# Face2.net
KiCad netlist of a schematic drawn in EAGLE
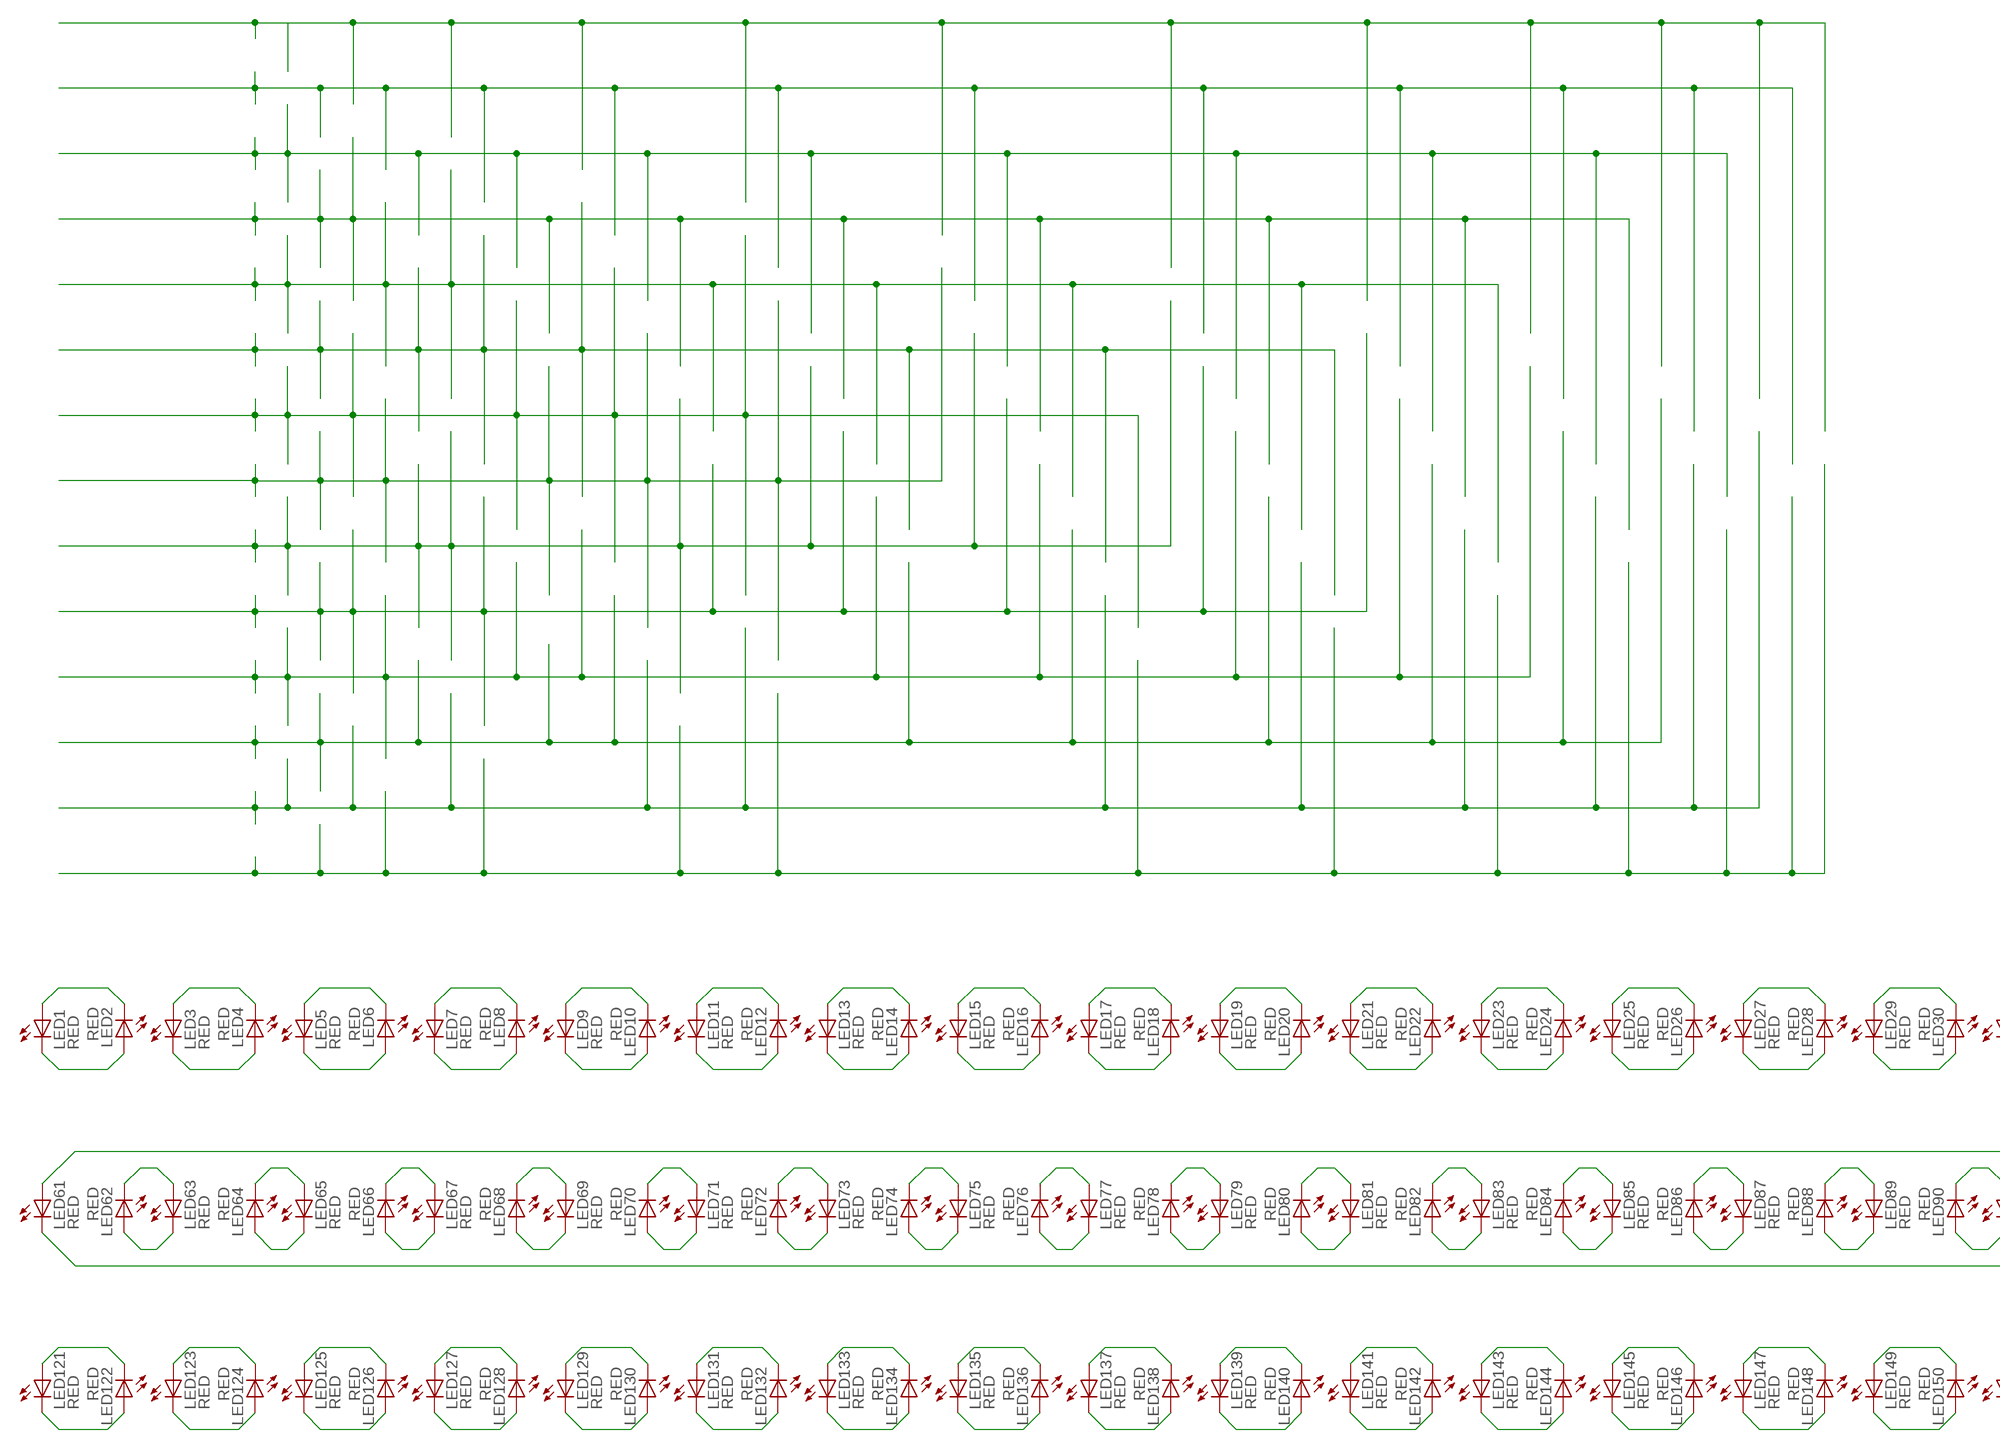
[diagram p0: schematic, sheet 1, part 1 of 2]
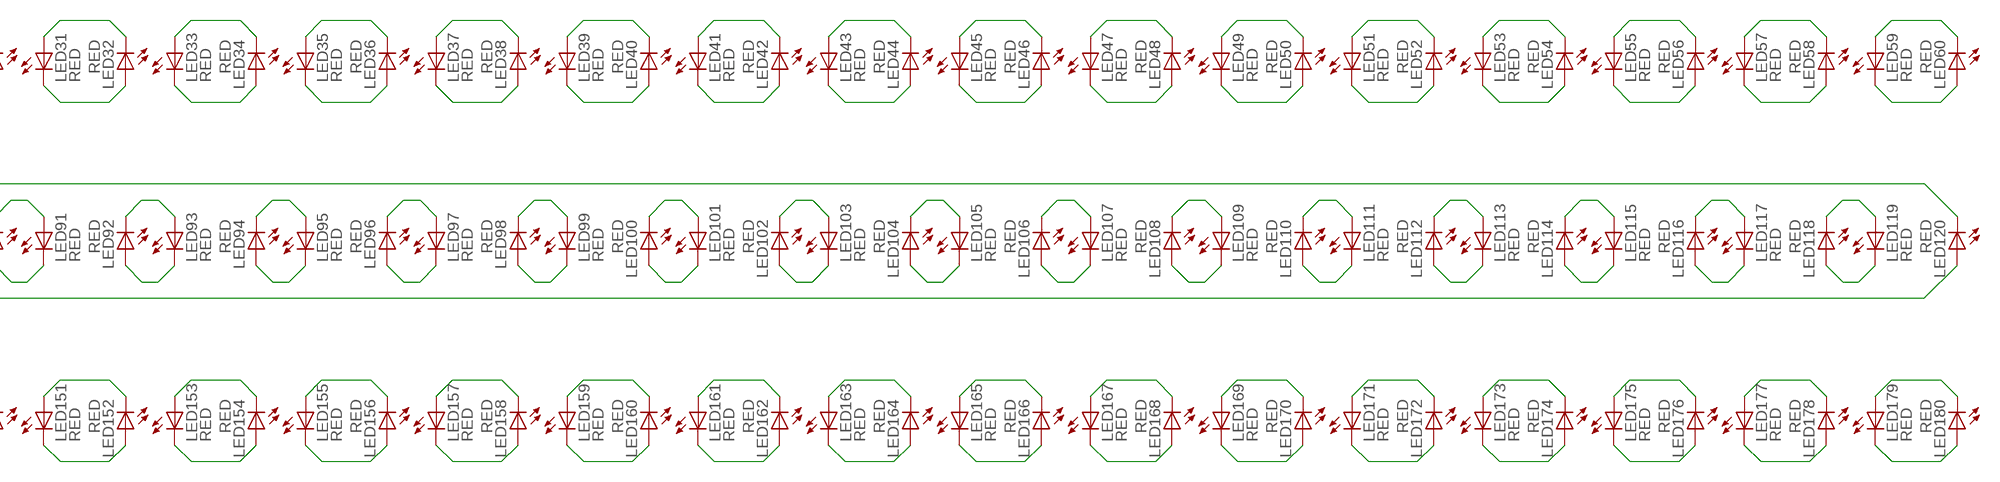
[diagram p1: schematic, sheet 1, part 2 of 2]

(export (version "E")
  (design (tool "Eeschema 10.0.6"))
  (components
    (comp (ref "LED1")
      (value "RED")
      (footprint "eagle-import:LED-0603")
      (libsource (lib "eagle-import") (part "LED0603"))
    )
    (comp (ref "LED2")
      (value "RED")
      (footprint "eagle-import:LED-0603")
      (libsource (lib "eagle-import") (part "LED0603"))
    )
    (comp (ref "LED3")
      (value "RED")
      (footprint "eagle-import:LED-0603")
      (libsource (lib "eagle-import") (part "LED0603"))
    )
    (comp (ref "LED4")
      (value "RED")
      (footprint "eagle-import:LED-0603")
      (libsource (lib "eagle-import") (part "LED0603"))
    )
    (comp (ref "LED5")
      (value "RED")
      (footprint "eagle-import:LED-0603")
      (libsource (lib "eagle-import") (part "LED0603"))
    )
    (comp (ref "LED6")
      (value "RED")
      (footprint "eagle-import:LED-0603")
      (libsource (lib "eagle-import") (part "LED0603"))
    )
    (comp (ref "LED7")
      (value "RED")
      (footprint "eagle-import:LED-0603")
      (libsource (lib "eagle-import") (part "LED0603"))
    )
    (comp (ref "LED8")
      (value "RED")
      (footprint "eagle-import:LED-0603")
      (libsource (lib "eagle-import") (part "LED0603"))
    )
    (comp (ref "LED9")
      (value "RED")
      (footprint "eagle-import:LED-0603")
      (libsource (lib "eagle-import") (part "LED0603"))
    )
    (comp (ref "LED10")
      (value "RED")
      (footprint "eagle-import:LED-0603")
      (libsource (lib "eagle-import") (part "LED0603"))
    )
    (comp (ref "LED11")
      (value "RED")
      (footprint "eagle-import:LED-0603")
      (libsource (lib "eagle-import") (part "LED0603"))
    )
    (comp (ref "LED12")
      (value "RED")
      (footprint "eagle-import:LED-0603")
      (libsource (lib "eagle-import") (part "LED0603"))
    )
    (comp (ref "LED13")
      (value "RED")
      (footprint "eagle-import:LED-0603")
      (libsource (lib "eagle-import") (part "LED0603"))
    )
    (comp (ref "LED14")
      (value "RED")
      (footprint "eagle-import:LED-0603")
      (libsource (lib "eagle-import") (part "LED0603"))
    )
    (comp (ref "LED15")
      (value "RED")
      (footprint "eagle-import:LED-0603")
      (libsource (lib "eagle-import") (part "LED0603"))
    )
    (comp (ref "LED16")
      (value "RED")
      (footprint "eagle-import:LED-0603")
      (libsource (lib "eagle-import") (part "LED0603"))
    )
    (comp (ref "LED17")
      (value "RED")
      (footprint "eagle-import:LED-0603")
      (libsource (lib "eagle-import") (part "LED0603"))
    )
    (comp (ref "LED18")
      (value "RED")
      (footprint "eagle-import:LED-0603")
      (libsource (lib "eagle-import") (part "LED0603"))
    )
    (comp (ref "LED19")
      (value "RED")
      (footprint "eagle-import:LED-0603")
      (libsource (lib "eagle-import") (part "LED0603"))
    )
    (comp (ref "LED20")
      (value "RED")
      (footprint "eagle-import:LED-0603")
      (libsource (lib "eagle-import") (part "LED0603"))
    )
    (comp (ref "LED21")
      (value "RED")
      (footprint "eagle-import:LED-0603")
      (libsource (lib "eagle-import") (part "LED0603"))
    )
    (comp (ref "LED22")
      (value "RED")
      (footprint "eagle-import:LED-0603")
      (libsource (lib "eagle-import") (part "LED0603"))
    )
    (comp (ref "LED23")
      (value "RED")
      (footprint "eagle-import:LED-0603")
      (libsource (lib "eagle-import") (part "LED0603"))
    )
    (comp (ref "LED24")
      (value "RED")
      (footprint "eagle-import:LED-0603")
      (libsource (lib "eagle-import") (part "LED0603"))
    )
    (comp (ref "LED25")
      (value "RED")
      (footprint "eagle-import:LED-0603")
      (libsource (lib "eagle-import") (part "LED0603"))
    )
    (comp (ref "LED26")
      (value "RED")
      (footprint "eagle-import:LED-0603")
      (libsource (lib "eagle-import") (part "LED0603"))
    )
    (comp (ref "LED27")
      (value "RED")
      (footprint "eagle-import:LED-0603")
      (libsource (lib "eagle-import") (part "LED0603"))
    )
    (comp (ref "LED28")
      (value "RED")
      (footprint "eagle-import:LED-0603")
      (libsource (lib "eagle-import") (part "LED0603"))
    )
    (comp (ref "LED29")
      (value "RED")
      (footprint "eagle-import:LED-0603")
      (libsource (lib "eagle-import") (part "LED0603"))
    )
    (comp (ref "LED30")
      (value "RED")
      (footprint "eagle-import:LED-0603")
      (libsource (lib "eagle-import") (part "LED0603"))
    )
    (comp (ref "LED31")
      (value "RED")
      (footprint "eagle-import:LED-0603")
      (libsource (lib "eagle-import") (part "LED0603"))
    )
    (comp (ref "LED32")
      (value "RED")
      (footprint "eagle-import:LED-0603")
      (libsource (lib "eagle-import") (part "LED0603"))
    )
    (comp (ref "LED33")
      (value "RED")
      (footprint "eagle-import:LED-0603")
      (libsource (lib "eagle-import") (part "LED0603"))
    )
    (comp (ref "LED34")
      (value "RED")
      (footprint "eagle-import:LED-0603")
      (libsource (lib "eagle-import") (part "LED0603"))
    )
    (comp (ref "LED35")
      (value "RED")
      (footprint "eagle-import:LED-0603")
      (libsource (lib "eagle-import") (part "LED0603"))
    )
    (comp (ref "LED36")
      (value "RED")
      (footprint "eagle-import:LED-0603")
      (libsource (lib "eagle-import") (part "LED0603"))
    )
    (comp (ref "LED37")
      (value "RED")
      (footprint "eagle-import:LED-0603")
      (libsource (lib "eagle-import") (part "LED0603"))
    )
    (comp (ref "LED38")
      (value "RED")
      (footprint "eagle-import:LED-0603")
      (libsource (lib "eagle-import") (part "LED0603"))
    )
    (comp (ref "LED39")
      (value "RED")
      (footprint "eagle-import:LED-0603")
      (libsource (lib "eagle-import") (part "LED0603"))
    )
    (comp (ref "LED40")
      (value "RED")
      (footprint "eagle-import:LED-0603")
      (libsource (lib "eagle-import") (part "LED0603"))
    )
    (comp (ref "LED41")
      (value "RED")
      (footprint "eagle-import:LED-0603")
      (libsource (lib "eagle-import") (part "LED0603"))
    )
    (comp (ref "LED42")
      (value "RED")
      (footprint "eagle-import:LED-0603")
      (libsource (lib "eagle-import") (part "LED0603"))
    )
    (comp (ref "LED43")
      (value "RED")
      (footprint "eagle-import:LED-0603")
      (libsource (lib "eagle-import") (part "LED0603"))
    )
    (comp (ref "LED44")
      (value "RED")
      (footprint "eagle-import:LED-0603")
      (libsource (lib "eagle-import") (part "LED0603"))
    )
    (comp (ref "LED45")
      (value "RED")
      (footprint "eagle-import:LED-0603")
      (libsource (lib "eagle-import") (part "LED0603"))
    )
    (comp (ref "LED46")
      (value "RED")
      (footprint "eagle-import:LED-0603")
      (libsource (lib "eagle-import") (part "LED0603"))
    )
    (comp (ref "LED47")
      (value "RED")
      (footprint "eagle-import:LED-0603")
      (libsource (lib "eagle-import") (part "LED0603"))
    )
    (comp (ref "LED48")
      (value "RED")
      (footprint "eagle-import:LED-0603")
      (libsource (lib "eagle-import") (part "LED0603"))
    )
    (comp (ref "LED49")
      (value "RED")
      (footprint "eagle-import:LED-0603")
      (libsource (lib "eagle-import") (part "LED0603"))
    )
    (comp (ref "LED50")
      (value "RED")
      (footprint "eagle-import:LED-0603")
      (libsource (lib "eagle-import") (part "LED0603"))
    )
    (comp (ref "LED51")
      (value "RED")
      (footprint "eagle-import:LED-0603")
      (libsource (lib "eagle-import") (part "LED0603"))
    )
    (comp (ref "LED52")
      (value "RED")
      (footprint "eagle-import:LED-0603")
      (libsource (lib "eagle-import") (part "LED0603"))
    )
    (comp (ref "LED53")
      (value "RED")
      (footprint "eagle-import:LED-0603")
      (libsource (lib "eagle-import") (part "LED0603"))
    )
    (comp (ref "LED54")
      (value "RED")
      (footprint "eagle-import:LED-0603")
      (libsource (lib "eagle-import") (part "LED0603"))
    )
    (comp (ref "LED55")
      (value "RED")
      (footprint "eagle-import:LED-0603")
      (libsource (lib "eagle-import") (part "LED0603"))
    )
    (comp (ref "LED56")
      (value "RED")
      (footprint "eagle-import:LED-0603")
      (libsource (lib "eagle-import") (part "LED0603"))
    )
    (comp (ref "LED57")
      (value "RED")
      (footprint "eagle-import:LED-0603")
      (libsource (lib "eagle-import") (part "LED0603"))
    )
    (comp (ref "LED58")
      (value "RED")
      (footprint "eagle-import:LED-0603")
      (libsource (lib "eagle-import") (part "LED0603"))
    )
    (comp (ref "LED59")
      (value "RED")
      (footprint "eagle-import:LED-0603")
      (libsource (lib "eagle-import") (part "LED0603"))
    )
    (comp (ref "LED60")
      (value "RED")
      (footprint "eagle-import:LED-0603")
      (libsource (lib "eagle-import") (part "LED0603"))
    )
    (comp (ref "LED61")
      (value "RED")
      (footprint "eagle-import:LED-0603")
      (libsource (lib "eagle-import") (part "LED0603"))
    )
    (comp (ref "LED62")
      (value "RED")
      (footprint "eagle-import:LED-0603")
      (libsource (lib "eagle-import") (part "LED0603"))
    )
    (comp (ref "LED63")
      (value "RED")
      (footprint "eagle-import:LED-0603")
      (libsource (lib "eagle-import") (part "LED0603"))
    )
    (comp (ref "LED64")
      (value "RED")
      (footprint "eagle-import:LED-0603")
      (libsource (lib "eagle-import") (part "LED0603"))
    )
    (comp (ref "LED65")
      (value "RED")
      (footprint "eagle-import:LED-0603")
      (libsource (lib "eagle-import") (part "LED0603"))
    )
    (comp (ref "LED66")
      (value "RED")
      (footprint "eagle-import:LED-0603")
      (libsource (lib "eagle-import") (part "LED0603"))
    )
    (comp (ref "LED67")
      (value "RED")
      (footprint "eagle-import:LED-0603")
      (libsource (lib "eagle-import") (part "LED0603"))
    )
    (comp (ref "LED68")
      (value "RED")
      (footprint "eagle-import:LED-0603")
      (libsource (lib "eagle-import") (part "LED0603"))
    )
    (comp (ref "LED69")
      (value "RED")
      (footprint "eagle-import:LED-0603")
      (libsource (lib "eagle-import") (part "LED0603"))
    )
    (comp (ref "LED70")
      (value "RED")
      (footprint "eagle-import:LED-0603")
      (libsource (lib "eagle-import") (part "LED0603"))
    )
    (comp (ref "LED71")
      (value "RED")
      (footprint "eagle-import:LED-0603")
      (libsource (lib "eagle-import") (part "LED0603"))
    )
    (comp (ref "LED72")
      (value "RED")
      (footprint "eagle-import:LED-0603")
      (libsource (lib "eagle-import") (part "LED0603"))
    )
    (comp (ref "LED73")
      (value "RED")
      (footprint "eagle-import:LED-0603")
      (libsource (lib "eagle-import") (part "LED0603"))
    )
    (comp (ref "LED74")
      (value "RED")
      (footprint "eagle-import:LED-0603")
      (libsource (lib "eagle-import") (part "LED0603"))
    )
    (comp (ref "LED75")
      (value "RED")
      (footprint "eagle-import:LED-0603")
      (libsource (lib "eagle-import") (part "LED0603"))
    )
    (comp (ref "LED76")
      (value "RED")
      (footprint "eagle-import:LED-0603")
      (libsource (lib "eagle-import") (part "LED0603"))
    )
    (comp (ref "LED77")
      (value "RED")
      (footprint "eagle-import:LED-0603")
      (libsource (lib "eagle-import") (part "LED0603"))
    )
    (comp (ref "LED78")
      (value "RED")
      (footprint "eagle-import:LED-0603")
      (libsource (lib "eagle-import") (part "LED0603"))
    )
    (comp (ref "LED79")
      (value "RED")
      (footprint "eagle-import:LED-0603")
      (libsource (lib "eagle-import") (part "LED0603"))
    )
    (comp (ref "LED80")
      (value "RED")
      (footprint "eagle-import:LED-0603")
      (libsource (lib "eagle-import") (part "LED0603"))
    )
    (comp (ref "LED81")
      (value "RED")
      (footprint "eagle-import:LED-0603")
      (libsource (lib "eagle-import") (part "LED0603"))
    )
    (comp (ref "LED82")
      (value "RED")
      (footprint "eagle-import:LED-0603")
      (libsource (lib "eagle-import") (part "LED0603"))
    )
    (comp (ref "LED83")
      (value "RED")
      (footprint "eagle-import:LED-0603")
      (libsource (lib "eagle-import") (part "LED0603"))
    )
    (comp (ref "LED84")
      (value "RED")
      (footprint "eagle-import:LED-0603")
      (libsource (lib "eagle-import") (part "LED0603"))
    )
    (comp (ref "LED85")
      (value "RED")
      (footprint "eagle-import:LED-0603")
      (libsource (lib "eagle-import") (part "LED0603"))
    )
    (comp (ref "LED86")
      (value "RED")
      (footprint "eagle-import:LED-0603")
      (libsource (lib "eagle-import") (part "LED0603"))
    )
    (comp (ref "LED87")
      (value "RED")
      (footprint "eagle-import:LED-0603")
      (libsource (lib "eagle-import") (part "LED0603"))
    )
    (comp (ref "LED88")
      (value "RED")
      (footprint "eagle-import:LED-0603")
      (libsource (lib "eagle-import") (part "LED0603"))
    )
    (comp (ref "LED89")
      (value "RED")
      (footprint "eagle-import:LED-0603")
      (libsource (lib "eagle-import") (part "LED0603"))
    )
    (comp (ref "LED90")
      (value "RED")
      (footprint "eagle-import:LED-0603")
      (libsource (lib "eagle-import") (part "LED0603"))
    )
    (comp (ref "LED91")
      (value "RED")
      (footprint "eagle-import:LED-0603")
      (libsource (lib "eagle-import") (part "LED0603"))
    )
    (comp (ref "LED92")
      (value "RED")
      (footprint "eagle-import:LED-0603")
      (libsource (lib "eagle-import") (part "LED0603"))
    )
    (comp (ref "LED93")
      (value "RED")
      (footprint "eagle-import:LED-0603")
      (libsource (lib "eagle-import") (part "LED0603"))
    )
    (comp (ref "LED94")
      (value "RED")
      (footprint "eagle-import:LED-0603")
      (libsource (lib "eagle-import") (part "LED0603"))
    )
    (comp (ref "LED95")
      (value "RED")
      (footprint "eagle-import:LED-0603")
      (libsource (lib "eagle-import") (part "LED0603"))
    )
    (comp (ref "LED96")
      (value "RED")
      (footprint "eagle-import:LED-0603")
      (libsource (lib "eagle-import") (part "LED0603"))
    )
    (comp (ref "LED97")
      (value "RED")
      (footprint "eagle-import:LED-0603")
      (libsource (lib "eagle-import") (part "LED0603"))
    )
    (comp (ref "LED98")
      (value "RED")
      (footprint "eagle-import:LED-0603")
      (libsource (lib "eagle-import") (part "LED0603"))
    )
    (comp (ref "LED99")
      (value "RED")
      (footprint "eagle-import:LED-0603")
      (libsource (lib "eagle-import") (part "LED0603"))
    )
    (comp (ref "LED100")
      (value "RED")
      (footprint "eagle-import:LED-0603")
      (libsource (lib "eagle-import") (part "LED0603"))
    )
    (comp (ref "LED101")
      (value "RED")
      (footprint "eagle-import:LED-0603")
      (libsource (lib "eagle-import") (part "LED0603"))
    )
    (comp (ref "LED102")
      (value "RED")
      (footprint "eagle-import:LED-0603")
      (libsource (lib "eagle-import") (part "LED0603"))
    )
    (comp (ref "LED103")
      (value "RED")
      (footprint "eagle-import:LED-0603")
      (libsource (lib "eagle-import") (part "LED0603"))
    )
    (comp (ref "LED104")
      (value "RED")
      (footprint "eagle-import:LED-0603")
      (libsource (lib "eagle-import") (part "LED0603"))
    )
    (comp (ref "LED105")
      (value "RED")
      (footprint "eagle-import:LED-0603")
      (libsource (lib "eagle-import") (part "LED0603"))
    )
    (comp (ref "LED106")
      (value "RED")
      (footprint "eagle-import:LED-0603")
      (libsource (lib "eagle-import") (part "LED0603"))
    )
    (comp (ref "LED107")
      (value "RED")
      (footprint "eagle-import:LED-0603")
      (libsource (lib "eagle-import") (part "LED0603"))
    )
    (comp (ref "LED108")
      (value "RED")
      (footprint "eagle-import:LED-0603")
      (libsource (lib "eagle-import") (part "LED0603"))
    )
    (comp (ref "LED109")
      (value "RED")
      (footprint "eagle-import:LED-0603")
      (libsource (lib "eagle-import") (part "LED0603"))
    )
    (comp (ref "LED110")
      (value "RED")
      (footprint "eagle-import:LED-0603")
      (libsource (lib "eagle-import") (part "LED0603"))
    )
    (comp (ref "LED111")
      (value "RED")
      (footprint "eagle-import:LED-0603")
      (libsource (lib "eagle-import") (part "LED0603"))
    )
    (comp (ref "LED112")
      (value "RED")
      (footprint "eagle-import:LED-0603")
      (libsource (lib "eagle-import") (part "LED0603"))
    )
    (comp (ref "LED113")
      (value "RED")
      (footprint "eagle-import:LED-0603")
      (libsource (lib "eagle-import") (part "LED0603"))
    )
    (comp (ref "LED114")
      (value "RED")
      (footprint "eagle-import:LED-0603")
      (libsource (lib "eagle-import") (part "LED0603"))
    )
    (comp (ref "LED115")
      (value "RED")
      (footprint "eagle-import:LED-0603")
      (libsource (lib "eagle-import") (part "LED0603"))
    )
    (comp (ref "LED116")
      (value "RED")
      (footprint "eagle-import:LED-0603")
      (libsource (lib "eagle-import") (part "LED0603"))
    )
    (comp (ref "LED117")
      (value "RED")
      (footprint "eagle-import:LED-0603")
      (libsource (lib "eagle-import") (part "LED0603"))
    )
    (comp (ref "LED118")
      (value "RED")
      (footprint "eagle-import:LED-0603")
      (libsource (lib "eagle-import") (part "LED0603"))
    )
    (comp (ref "LED119")
      (value "RED")
      (footprint "eagle-import:LED-0603")
      (libsource (lib "eagle-import") (part "LED0603"))
    )
    (comp (ref "LED120")
      (value "RED")
      (footprint "eagle-import:LED-0603")
      (libsource (lib "eagle-import") (part "LED0603"))
    )
    (comp (ref "LED121")
      (value "RED")
      (footprint "eagle-import:LED-0603")
      (libsource (lib "eagle-import") (part "LED0603"))
    )
    (comp (ref "LED122")
      (value "RED")
      (footprint "eagle-import:LED-0603")
      (libsource (lib "eagle-import") (part "LED0603"))
    )
    (comp (ref "LED123")
      (value "RED")
      (footprint "eagle-import:LED-0603")
      (libsource (lib "eagle-import") (part "LED0603"))
    )
    (comp (ref "LED124")
      (value "RED")
      (footprint "eagle-import:LED-0603")
      (libsource (lib "eagle-import") (part "LED0603"))
    )
    (comp (ref "LED125")
      (value "RED")
      (footprint "eagle-import:LED-0603")
      (libsource (lib "eagle-import") (part "LED0603"))
    )
    (comp (ref "LED126")
      (value "RED")
      (footprint "eagle-import:LED-0603")
      (libsource (lib "eagle-import") (part "LED0603"))
    )
    (comp (ref "LED127")
      (value "RED")
      (footprint "eagle-import:LED-0603")
      (libsource (lib "eagle-import") (part "LED0603"))
    )
    (comp (ref "LED128")
      (value "RED")
      (footprint "eagle-import:LED-0603")
      (libsource (lib "eagle-import") (part "LED0603"))
    )
    (comp (ref "LED129")
      (value "RED")
      (footprint "eagle-import:LED-0603")
      (libsource (lib "eagle-import") (part "LED0603"))
    )
    (comp (ref "LED130")
      (value "RED")
      (footprint "eagle-import:LED-0603")
      (libsource (lib "eagle-import") (part "LED0603"))
    )
    (comp (ref "LED131")
      (value "RED")
      (footprint "eagle-import:LED-0603")
      (libsource (lib "eagle-import") (part "LED0603"))
    )
    (comp (ref "LED132")
      (value "RED")
      (footprint "eagle-import:LED-0603")
      (libsource (lib "eagle-import") (part "LED0603"))
    )
    (comp (ref "LED133")
      (value "RED")
      (footprint "eagle-import:LED-0603")
      (libsource (lib "eagle-import") (part "LED0603"))
    )
    (comp (ref "LED134")
      (value "RED")
      (footprint "eagle-import:LED-0603")
      (libsource (lib "eagle-import") (part "LED0603"))
    )
    (comp (ref "LED135")
      (value "RED")
      (footprint "eagle-import:LED-0603")
      (libsource (lib "eagle-import") (part "LED0603"))
    )
    (comp (ref "LED136")
      (value "RED")
      (footprint "eagle-import:LED-0603")
      (libsource (lib "eagle-import") (part "LED0603"))
    )
    (comp (ref "LED137")
      (value "RED")
      (footprint "eagle-import:LED-0603")
      (libsource (lib "eagle-import") (part "LED0603"))
    )
    (comp (ref "LED138")
      (value "RED")
      (footprint "eagle-import:LED-0603")
      (libsource (lib "eagle-import") (part "LED0603"))
    )
    (comp (ref "LED139")
      (value "RED")
      (footprint "eagle-import:LED-0603")
      (libsource (lib "eagle-import") (part "LED0603"))
    )
    (comp (ref "LED140")
      (value "RED")
      (footprint "eagle-import:LED-0603")
      (libsource (lib "eagle-import") (part "LED0603"))
    )
    (comp (ref "LED141")
      (value "RED")
      (footprint "eagle-import:LED-0603")
      (libsource (lib "eagle-import") (part "LED0603"))
    )
    (comp (ref "LED142")
      (value "RED")
      (footprint "eagle-import:LED-0603")
      (libsource (lib "eagle-import") (part "LED0603"))
    )
    (comp (ref "LED143")
      (value "RED")
      (footprint "eagle-import:LED-0603")
      (libsource (lib "eagle-import") (part "LED0603"))
    )
    (comp (ref "LED144")
      (value "RED")
      (footprint "eagle-import:LED-0603")
      (libsource (lib "eagle-import") (part "LED0603"))
    )
    (comp (ref "LED145")
      (value "RED")
      (footprint "eagle-import:LED-0603")
      (libsource (lib "eagle-import") (part "LED0603"))
    )
    (comp (ref "LED146")
      (value "RED")
      (footprint "eagle-import:LED-0603")
      (libsource (lib "eagle-import") (part "LED0603"))
    )
    (comp (ref "LED147")
      (value "RED")
      (footprint "eagle-import:LED-0603")
      (libsource (lib "eagle-import") (part "LED0603"))
    )
    (comp (ref "LED148")
      (value "RED")
      (footprint "eagle-import:LED-0603")
      (libsource (lib "eagle-import") (part "LED0603"))
    )
    (comp (ref "LED149")
      (value "RED")
      (footprint "eagle-import:LED-0603")
      (libsource (lib "eagle-import") (part "LED0603"))
    )
    (comp (ref "LED150")
      (value "RED")
      (footprint "eagle-import:LED-0603")
      (libsource (lib "eagle-import") (part "LED0603"))
    )
    (comp (ref "LED151")
      (value "RED")
      (footprint "eagle-import:LED-0603")
      (libsource (lib "eagle-import") (part "LED0603"))
    )
    (comp (ref "LED152")
      (value "RED")
      (footprint "eagle-import:LED-0603")
      (libsource (lib "eagle-import") (part "LED0603"))
    )
    (comp (ref "LED153")
      (value "RED")
      (footprint "eagle-import:LED-0603")
      (libsource (lib "eagle-import") (part "LED0603"))
    )
    (comp (ref "LED154")
      (value "RED")
      (footprint "eagle-import:LED-0603")
      (libsource (lib "eagle-import") (part "LED0603"))
    )
    (comp (ref "LED155")
      (value "RED")
      (footprint "eagle-import:LED-0603")
      (libsource (lib "eagle-import") (part "LED0603"))
    )
    (comp (ref "LED156")
      (value "RED")
      (footprint "eagle-import:LED-0603")
      (libsource (lib "eagle-import") (part "LED0603"))
    )
    (comp (ref "LED157")
      (value "RED")
      (footprint "eagle-import:LED-0603")
      (libsource (lib "eagle-import") (part "LED0603"))
    )
    (comp (ref "LED158")
      (value "RED")
      (footprint "eagle-import:LED-0603")
      (libsource (lib "eagle-import") (part "LED0603"))
    )
    (comp (ref "LED159")
      (value "RED")
      (footprint "eagle-import:LED-0603")
      (libsource (lib "eagle-import") (part "LED0603"))
    )
    (comp (ref "LED160")
      (value "RED")
      (footprint "eagle-import:LED-0603")
      (libsource (lib "eagle-import") (part "LED0603"))
    )
    (comp (ref "LED161")
      (value "RED")
      (footprint "eagle-import:LED-0603")
      (libsource (lib "eagle-import") (part "LED0603"))
    )
    (comp (ref "LED162")
      (value "RED")
      (footprint "eagle-import:LED-0603")
      (libsource (lib "eagle-import") (part "LED0603"))
    )
    (comp (ref "LED163")
      (value "RED")
      (footprint "eagle-import:LED-0603")
      (libsource (lib "eagle-import") (part "LED0603"))
    )
    (comp (ref "LED164")
      (value "RED")
      (footprint "eagle-import:LED-0603")
      (libsource (lib "eagle-import") (part "LED0603"))
    )
    (comp (ref "LED165")
      (value "RED")
      (footprint "eagle-import:LED-0603")
      (libsource (lib "eagle-import") (part "LED0603"))
    )
    (comp (ref "LED166")
      (value "RED")
      (footprint "eagle-import:LED-0603")
      (libsource (lib "eagle-import") (part "LED0603"))
    )
    (comp (ref "LED167")
      (value "RED")
      (footprint "eagle-import:LED-0603")
      (libsource (lib "eagle-import") (part "LED0603"))
    )
    (comp (ref "LED168")
      (value "RED")
      (footprint "eagle-import:LED-0603")
      (libsource (lib "eagle-import") (part "LED0603"))
    )
    (comp (ref "LED169")
      (value "RED")
      (footprint "eagle-import:LED-0603")
      (libsource (lib "eagle-import") (part "LED0603"))
    )
    (comp (ref "LED170")
      (value "RED")
      (footprint "eagle-import:LED-0603")
      (libsource (lib "eagle-import") (part "LED0603"))
    )
    (comp (ref "LED171")
      (value "RED")
      (footprint "eagle-import:LED-0603")
      (libsource (lib "eagle-import") (part "LED0603"))
    )
    (comp (ref "LED172")
      (value "RED")
      (footprint "eagle-import:LED-0603")
      (libsource (lib "eagle-import") (part "LED0603"))
    )
    (comp (ref "LED173")
      (value "RED")
      (footprint "eagle-import:LED-0603")
      (libsource (lib "eagle-import") (part "LED0603"))
    )
    (comp (ref "LED174")
      (value "RED")
      (footprint "eagle-import:LED-0603")
      (libsource (lib "eagle-import") (part "LED0603"))
    )
    (comp (ref "LED175")
      (value "RED")
      (footprint "eagle-import:LED-0603")
      (libsource (lib "eagle-import") (part "LED0603"))
    )
    (comp (ref "LED176")
      (value "RED")
      (footprint "eagle-import:LED-0603")
      (libsource (lib "eagle-import") (part "LED0603"))
    )
    (comp (ref "LED177")
      (value "RED")
      (footprint "eagle-import:LED-0603")
      (libsource (lib "eagle-import") (part "LED0603"))
    )
    (comp (ref "LED178")
      (value "RED")
      (footprint "eagle-import:LED-0603")
      (libsource (lib "eagle-import") (part "LED0603"))
    )
    (comp (ref "LED179")
      (value "RED")
      (footprint "eagle-import:LED-0603")
      (libsource (lib "eagle-import") (part "LED0603"))
    )
    (comp (ref "LED180")
      (value "RED")
      (footprint "eagle-import:LED-0603")
      (libsource (lib "eagle-import") (part "LED0603"))
    )
  )
  (nets
    (net (code "1") (name "Net-(LED1-PadA)") (class "Default")
      (node (ref "LED1") (pin "A") (pinfunction "A_A") (pintype "passive"))
      (node (ref "LED2") (pin "C") (pinfunction "C_C") (pintype "passive"))
    )
    (net (code "2") (name "Net-(LED1-PadC)") (class "Default")
      (node (ref "LED1") (pin "C") (pinfunction "C_C") (pintype "passive"))
      (node (ref "LED2") (pin "A") (pinfunction "A_A") (pintype "passive"))
    )
    (net (code "3") (name "Net-(LED3-PadA)") (class "Default")
      (node (ref "LED3") (pin "A") (pinfunction "A_A") (pintype "passive"))
      (node (ref "LED4") (pin "C") (pinfunction "C_C") (pintype "passive"))
    )
    (net (code "4") (name "Net-(LED3-PadC)") (class "Default")
      (node (ref "LED3") (pin "C") (pinfunction "C_C") (pintype "passive"))
      (node (ref "LED4") (pin "A") (pinfunction "A_A") (pintype "passive"))
    )
    (net (code "5") (name "Net-(LED5-PadA)") (class "Default")
      (node (ref "LED5") (pin "A") (pinfunction "A_A") (pintype "passive"))
      (node (ref "LED6") (pin "C") (pinfunction "C_C") (pintype "passive"))
    )
    (net (code "6") (name "Net-(LED5-PadC)") (class "Default")
      (node (ref "LED5") (pin "C") (pinfunction "C_C") (pintype "passive"))
      (node (ref "LED6") (pin "A") (pinfunction "A_A") (pintype "passive"))
    )
    (net (code "7") (name "Net-(LED7-PadA)") (class "Default")
      (node (ref "LED7") (pin "A") (pinfunction "A_A") (pintype "passive"))
      (node (ref "LED8") (pin "C") (pinfunction "C_C") (pintype "passive"))
    )
    (net (code "8") (name "Net-(LED7-PadC)") (class "Default")
      (node (ref "LED7") (pin "C") (pinfunction "C_C") (pintype "passive"))
      (node (ref "LED8") (pin "A") (pinfunction "A_A") (pintype "passive"))
    )
    (net (code "9") (name "Net-(LED10-PadA)") (class "Default")
      (node (ref "LED10") (pin "A") (pinfunction "A_A") (pintype "passive"))
      (node (ref "LED9") (pin "C") (pinfunction "C_C") (pintype "passive"))
    )
    (net (code "10") (name "Net-(LED10-PadC)") (class "Default")
      (node (ref "LED10") (pin "C") (pinfunction "C_C") (pintype "passive"))
      (node (ref "LED9") (pin "A") (pinfunction "A_A") (pintype "passive"))
    )
    (net (code "11") (name "Net-(LED11-PadA)") (class "Default")
      (node (ref "LED11") (pin "A") (pinfunction "A_A") (pintype "passive"))
      (node (ref "LED12") (pin "C") (pinfunction "C_C") (pintype "passive"))
    )
    (net (code "12") (name "Net-(LED11-PadC)") (class "Default")
      (node (ref "LED11") (pin "C") (pinfunction "C_C") (pintype "passive"))
      (node (ref "LED12") (pin "A") (pinfunction "A_A") (pintype "passive"))
    )
    (net (code "13") (name "Net-(LED13-PadA)") (class "Default")
      (node (ref "LED13") (pin "A") (pinfunction "A_A") (pintype "passive"))
      (node (ref "LED14") (pin "C") (pinfunction "C_C") (pintype "passive"))
    )
    (net (code "14") (name "Net-(LED13-PadC)") (class "Default")
      (node (ref "LED13") (pin "C") (pinfunction "C_C") (pintype "passive"))
      (node (ref "LED14") (pin "A") (pinfunction "A_A") (pintype "passive"))
    )
    (net (code "15") (name "Net-(LED15-PadA)") (class "Default")
      (node (ref "LED15") (pin "A") (pinfunction "A_A") (pintype "passive"))
      (node (ref "LED16") (pin "C") (pinfunction "C_C") (pintype "passive"))
    )
    (net (code "16") (name "Net-(LED15-PadC)") (class "Default")
      (node (ref "LED15") (pin "C") (pinfunction "C_C") (pintype "passive"))
      (node (ref "LED16") (pin "A") (pinfunction "A_A") (pintype "passive"))
    )
    (net (code "17") (name "Net-(LED17-PadA)") (class "Default")
      (node (ref "LED17") (pin "A") (pinfunction "A_A") (pintype "passive"))
      (node (ref "LED18") (pin "C") (pinfunction "C_C") (pintype "passive"))
    )
    (net (code "18") (name "Net-(LED17-PadC)") (class "Default")
      (node (ref "LED17") (pin "C") (pinfunction "C_C") (pintype "passive"))
      (node (ref "LED18") (pin "A") (pinfunction "A_A") (pintype "passive"))
    )
    (net (code "19") (name "Net-(LED19-PadA)") (class "Default")
      (node (ref "LED19") (pin "A") (pinfunction "A_A") (pintype "passive"))
      (node (ref "LED20") (pin "C") (pinfunction "C_C") (pintype "passive"))
    )
    (net (code "20") (name "Net-(LED19-PadC)") (class "Default")
      (node (ref "LED19") (pin "C") (pinfunction "C_C") (pintype "passive"))
      (node (ref "LED20") (pin "A") (pinfunction "A_A") (pintype "passive"))
    )
    (net (code "21") (name "Net-(LED21-PadA)") (class "Default")
      (node (ref "LED21") (pin "A") (pinfunction "A_A") (pintype "passive"))
      (node (ref "LED22") (pin "C") (pinfunction "C_C") (pintype "passive"))
    )
    (net (code "22") (name "Net-(LED21-PadC)") (class "Default")
      (node (ref "LED21") (pin "C") (pinfunction "C_C") (pintype "passive"))
      (node (ref "LED22") (pin "A") (pinfunction "A_A") (pintype "passive"))
    )
    (net (code "23") (name "Net-(LED23-PadA)") (class "Default")
      (node (ref "LED23") (pin "A") (pinfunction "A_A") (pintype "passive"))
      (node (ref "LED24") (pin "C") (pinfunction "C_C") (pintype "passive"))
    )
    (net (code "24") (name "Net-(LED23-PadC)") (class "Default")
      (node (ref "LED23") (pin "C") (pinfunction "C_C") (pintype "passive"))
      (node (ref "LED24") (pin "A") (pinfunction "A_A") (pintype "passive"))
    )
    (net (code "25") (name "Net-(LED25-PadA)") (class "Default")
      (node (ref "LED25") (pin "A") (pinfunction "A_A") (pintype "passive"))
      (node (ref "LED26") (pin "C") (pinfunction "C_C") (pintype "passive"))
    )
    (net (code "26") (name "Net-(LED25-PadC)") (class "Default")
      (node (ref "LED25") (pin "C") (pinfunction "C_C") (pintype "passive"))
      (node (ref "LED26") (pin "A") (pinfunction "A_A") (pintype "passive"))
    )
    (net (code "27") (name "Net-(LED27-PadA)") (class "Default")
      (node (ref "LED27") (pin "A") (pinfunction "A_A") (pintype "passive"))
      (node (ref "LED28") (pin "C") (pinfunction "C_C") (pintype "passive"))
    )
    (net (code "28") (name "Net-(LED27-PadC)") (class "Default")
      (node (ref "LED27") (pin "C") (pinfunction "C_C") (pintype "passive"))
      (node (ref "LED28") (pin "A") (pinfunction "A_A") (pintype "passive"))
    )
    (net (code "29") (name "Net-(LED29-PadA)") (class "Default")
      (node (ref "LED29") (pin "A") (pinfunction "A_A") (pintype "passive"))
      (node (ref "LED30") (pin "C") (pinfunction "C_C") (pintype "passive"))
    )
    (net (code "30") (name "Net-(LED29-PadC)") (class "Default")
      (node (ref "LED29") (pin "C") (pinfunction "C_C") (pintype "passive"))
      (node (ref "LED30") (pin "A") (pinfunction "A_A") (pintype "passive"))
    )
    (net (code "31") (name "Net-(LED31-PadA)") (class "Default")
      (node (ref "LED31") (pin "A") (pinfunction "A_A") (pintype "passive"))
      (node (ref "LED32") (pin "C") (pinfunction "C_C") (pintype "passive"))
    )
    (net (code "32") (name "Net-(LED31-PadC)") (class "Default")
      (node (ref "LED31") (pin "C") (pinfunction "C_C") (pintype "passive"))
      (node (ref "LED32") (pin "A") (pinfunction "A_A") (pintype "passive"))
    )
    (net (code "33") (name "Net-(LED33-PadA)") (class "Default")
      (node (ref "LED33") (pin "A") (pinfunction "A_A") (pintype "passive"))
      (node (ref "LED34") (pin "C") (pinfunction "C_C") (pintype "passive"))
    )
    (net (code "34") (name "Net-(LED33-PadC)") (class "Default")
      (node (ref "LED33") (pin "C") (pinfunction "C_C") (pintype "passive"))
      (node (ref "LED34") (pin "A") (pinfunction "A_A") (pintype "passive"))
    )
    (net (code "35") (name "Net-(LED35-PadA)") (class "Default")
      (node (ref "LED35") (pin "A") (pinfunction "A_A") (pintype "passive"))
      (node (ref "LED36") (pin "C") (pinfunction "C_C") (pintype "passive"))
    )
    (net (code "36") (name "Net-(LED35-PadC)") (class "Default")
      (node (ref "LED35") (pin "C") (pinfunction "C_C") (pintype "passive"))
      (node (ref "LED36") (pin "A") (pinfunction "A_A") (pintype "passive"))
    )
    (net (code "37") (name "Net-(LED37-PadA)") (class "Default")
      (node (ref "LED37") (pin "A") (pinfunction "A_A") (pintype "passive"))
      (node (ref "LED38") (pin "C") (pinfunction "C_C") (pintype "passive"))
    )
    (net (code "38") (name "Net-(LED37-PadC)") (class "Default")
      (node (ref "LED37") (pin "C") (pinfunction "C_C") (pintype "passive"))
      (node (ref "LED38") (pin "A") (pinfunction "A_A") (pintype "passive"))
    )
    (net (code "39") (name "Net-(LED39-PadA)") (class "Default")
      (node (ref "LED39") (pin "A") (pinfunction "A_A") (pintype "passive"))
      (node (ref "LED40") (pin "C") (pinfunction "C_C") (pintype "passive"))
    )
    (net (code "40") (name "Net-(LED39-PadC)") (class "Default")
      (node (ref "LED39") (pin "C") (pinfunction "C_C") (pintype "passive"))
      (node (ref "LED40") (pin "A") (pinfunction "A_A") (pintype "passive"))
    )
    (net (code "41") (name "Net-(LED41-PadA)") (class "Default")
      (node (ref "LED41") (pin "A") (pinfunction "A_A") (pintype "passive"))
      (node (ref "LED42") (pin "C") (pinfunction "C_C") (pintype "passive"))
    )
    (net (code "42") (name "Net-(LED41-PadC)") (class "Default")
      (node (ref "LED41") (pin "C") (pinfunction "C_C") (pintype "passive"))
      (node (ref "LED42") (pin "A") (pinfunction "A_A") (pintype "passive"))
    )
    (net (code "43") (name "Net-(LED43-PadA)") (class "Default")
      (node (ref "LED43") (pin "A") (pinfunction "A_A") (pintype "passive"))
      (node (ref "LED44") (pin "C") (pinfunction "C_C") (pintype "passive"))
    )
    (net (code "44") (name "Net-(LED43-PadC)") (class "Default")
      (node (ref "LED43") (pin "C") (pinfunction "C_C") (pintype "passive"))
      (node (ref "LED44") (pin "A") (pinfunction "A_A") (pintype "passive"))
    )
    (net (code "45") (name "Net-(LED45-PadA)") (class "Default")
      (node (ref "LED45") (pin "A") (pinfunction "A_A") (pintype "passive"))
      (node (ref "LED46") (pin "C") (pinfunction "C_C") (pintype "passive"))
    )
    (net (code "46") (name "Net-(LED45-PadC)") (class "Default")
      (node (ref "LED45") (pin "C") (pinfunction "C_C") (pintype "passive"))
      (node (ref "LED46") (pin "A") (pinfunction "A_A") (pintype "passive"))
    )
    (net (code "47") (name "Net-(LED47-PadA)") (class "Default")
      (node (ref "LED47") (pin "A") (pinfunction "A_A") (pintype "passive"))
      (node (ref "LED48") (pin "C") (pinfunction "C_C") (pintype "passive"))
    )
    (net (code "48") (name "Net-(LED47-PadC)") (class "Default")
      (node (ref "LED47") (pin "C") (pinfunction "C_C") (pintype "passive"))
      (node (ref "LED48") (pin "A") (pinfunction "A_A") (pintype "passive"))
    )
    (net (code "49") (name "Net-(LED49-PadA)") (class "Default")
      (node (ref "LED49") (pin "A") (pinfunction "A_A") (pintype "passive"))
      (node (ref "LED50") (pin "C") (pinfunction "C_C") (pintype "passive"))
    )
    (net (code "50") (name "Net-(LED49-PadC)") (class "Default")
      (node (ref "LED49") (pin "C") (pinfunction "C_C") (pintype "passive"))
      (node (ref "LED50") (pin "A") (pinfunction "A_A") (pintype "passive"))
    )
    (net (code "51") (name "Net-(LED51-PadA)") (class "Default")
      (node (ref "LED51") (pin "A") (pinfunction "A_A") (pintype "passive"))
      (node (ref "LED52") (pin "C") (pinfunction "C_C") (pintype "passive"))
    )
    (net (code "52") (name "Net-(LED51-PadC)") (class "Default")
      (node (ref "LED51") (pin "C") (pinfunction "C_C") (pintype "passive"))
      (node (ref "LED52") (pin "A") (pinfunction "A_A") (pintype "passive"))
    )
    (net (code "53") (name "Net-(LED53-PadA)") (class "Default")
      (node (ref "LED53") (pin "A") (pinfunction "A_A") (pintype "passive"))
      (node (ref "LED54") (pin "C") (pinfunction "C_C") (pintype "passive"))
    )
    (net (code "54") (name "Net-(LED53-PadC)") (class "Default")
      (node (ref "LED53") (pin "C") (pinfunction "C_C") (pintype "passive"))
      (node (ref "LED54") (pin "A") (pinfunction "A_A") (pintype "passive"))
    )
    (net (code "55") (name "Net-(LED55-PadA)") (class "Default")
      (node (ref "LED55") (pin "A") (pinfunction "A_A") (pintype "passive"))
      (node (ref "LED56") (pin "C") (pinfunction "C_C") (pintype "passive"))
    )
    (net (code "56") (name "Net-(LED55-PadC)") (class "Default")
      (node (ref "LED55") (pin "C") (pinfunction "C_C") (pintype "passive"))
      (node (ref "LED56") (pin "A") (pinfunction "A_A") (pintype "passive"))
    )
    (net (code "57") (name "Net-(LED57-PadA)") (class "Default")
      (node (ref "LED57") (pin "A") (pinfunction "A_A") (pintype "passive"))
      (node (ref "LED58") (pin "C") (pinfunction "C_C") (pintype "passive"))
    )
    (net (code "58") (name "Net-(LED57-PadC)") (class "Default")
      (node (ref "LED57") (pin "C") (pinfunction "C_C") (pintype "passive"))
      (node (ref "LED58") (pin "A") (pinfunction "A_A") (pintype "passive"))
    )
    (net (code "59") (name "Net-(LED59-PadA)") (class "Default")
      (node (ref "LED59") (pin "A") (pinfunction "A_A") (pintype "passive"))
      (node (ref "LED60") (pin "C") (pinfunction "C_C") (pintype "passive"))
    )
    (net (code "60") (name "Net-(LED59-PadC)") (class "Default")
      (node (ref "LED59") (pin "C") (pinfunction "C_C") (pintype "passive"))
      (node (ref "LED60") (pin "A") (pinfunction "A_A") (pintype "passive"))
    )
    (net (code "61") (name "Net-(LED62-PadA)") (class "Default")
      (node (ref "LED62") (pin "A") (pinfunction "A_A") (pintype "passive"))
      (node (ref "LED63") (pin "C") (pinfunction "C_C") (pintype "passive"))
    )
    (net (code "62") (name "Net-(LED62-PadC)") (class "Default")
      (node (ref "LED62") (pin "C") (pinfunction "C_C") (pintype "passive"))
      (node (ref "LED63") (pin "A") (pinfunction "A_A") (pintype "passive"))
    )
    (net (code "63") (name "Net-(LED64-PadA)") (class "Default")
      (node (ref "LED64") (pin "A") (pinfunction "A_A") (pintype "passive"))
      (node (ref "LED65") (pin "C") (pinfunction "C_C") (pintype "passive"))
    )
    (net (code "64") (name "Net-(LED64-PadC)") (class "Default")
      (node (ref "LED64") (pin "C") (pinfunction "C_C") (pintype "passive"))
      (node (ref "LED65") (pin "A") (pinfunction "A_A") (pintype "passive"))
    )
    (net (code "65") (name "Net-(LED66-PadA)") (class "Default")
      (node (ref "LED66") (pin "A") (pinfunction "A_A") (pintype "passive"))
      (node (ref "LED67") (pin "C") (pinfunction "C_C") (pintype "passive"))
    )
    (net (code "66") (name "Net-(LED66-PadC)") (class "Default")
      (node (ref "LED66") (pin "C") (pinfunction "C_C") (pintype "passive"))
      (node (ref "LED67") (pin "A") (pinfunction "A_A") (pintype "passive"))
    )
    (net (code "67") (name "Net-(LED68-PadA)") (class "Default")
      (node (ref "LED68") (pin "A") (pinfunction "A_A") (pintype "passive"))
      (node (ref "LED69") (pin "C") (pinfunction "C_C") (pintype "passive"))
    )
    (net (code "68") (name "Net-(LED68-PadC)") (class "Default")
      (node (ref "LED68") (pin "C") (pinfunction "C_C") (pintype "passive"))
      (node (ref "LED69") (pin "A") (pinfunction "A_A") (pintype "passive"))
    )
    (net (code "69") (name "Net-(LED70-PadA)") (class "Default")
      (node (ref "LED70") (pin "A") (pinfunction "A_A") (pintype "passive"))
      (node (ref "LED71") (pin "C") (pinfunction "C_C") (pintype "passive"))
    )
    (net (code "70") (name "Net-(LED70-PadC)") (class "Default")
      (node (ref "LED70") (pin "C") (pinfunction "C_C") (pintype "passive"))
      (node (ref "LED71") (pin "A") (pinfunction "A_A") (pintype "passive"))
    )
    (net (code "71") (name "Net-(LED72-PadA)") (class "Default")
      (node (ref "LED72") (pin "A") (pinfunction "A_A") (pintype "passive"))
      (node (ref "LED73") (pin "C") (pinfunction "C_C") (pintype "passive"))
    )
    (net (code "72") (name "Net-(LED72-PadC)") (class "Default")
      (node (ref "LED72") (pin "C") (pinfunction "C_C") (pintype "passive"))
      (node (ref "LED73") (pin "A") (pinfunction "A_A") (pintype "passive"))
    )
    (net (code "73") (name "Net-(LED74-PadA)") (class "Default")
      (node (ref "LED74") (pin "A") (pinfunction "A_A") (pintype "passive"))
      (node (ref "LED75") (pin "C") (pinfunction "C_C") (pintype "passive"))
    )
    (net (code "74") (name "Net-(LED74-PadC)") (class "Default")
      (node (ref "LED74") (pin "C") (pinfunction "C_C") (pintype "passive"))
      (node (ref "LED75") (pin "A") (pinfunction "A_A") (pintype "passive"))
    )
    (net (code "75") (name "Net-(LED76-PadA)") (class "Default")
      (node (ref "LED76") (pin "A") (pinfunction "A_A") (pintype "passive"))
      (node (ref "LED77") (pin "C") (pinfunction "C_C") (pintype "passive"))
    )
    (net (code "76") (name "Net-(LED76-PadC)") (class "Default")
      (node (ref "LED76") (pin "C") (pinfunction "C_C") (pintype "passive"))
      (node (ref "LED77") (pin "A") (pinfunction "A_A") (pintype "passive"))
    )
    (net (code "77") (name "Net-(LED78-PadA)") (class "Default")
      (node (ref "LED78") (pin "A") (pinfunction "A_A") (pintype "passive"))
      (node (ref "LED79") (pin "C") (pinfunction "C_C") (pintype "passive"))
    )
    (net (code "78") (name "Net-(LED78-PadC)") (class "Default")
      (node (ref "LED78") (pin "C") (pinfunction "C_C") (pintype "passive"))
      (node (ref "LED79") (pin "A") (pinfunction "A_A") (pintype "passive"))
    )
    (net (code "79") (name "Net-(LED80-PadA)") (class "Default")
      (node (ref "LED80") (pin "A") (pinfunction "A_A") (pintype "passive"))
      (node (ref "LED81") (pin "C") (pinfunction "C_C") (pintype "passive"))
    )
    (net (code "80") (name "Net-(LED80-PadC)") (class "Default")
      (node (ref "LED80") (pin "C") (pinfunction "C_C") (pintype "passive"))
      (node (ref "LED81") (pin "A") (pinfunction "A_A") (pintype "passive"))
    )
    (net (code "81") (name "Net-(LED82-PadA)") (class "Default")
      (node (ref "LED82") (pin "A") (pinfunction "A_A") (pintype "passive"))
      (node (ref "LED83") (pin "C") (pinfunction "C_C") (pintype "passive"))
    )
    (net (code "82") (name "Net-(LED82-PadC)") (class "Default")
      (node (ref "LED82") (pin "C") (pinfunction "C_C") (pintype "passive"))
      (node (ref "LED83") (pin "A") (pinfunction "A_A") (pintype "passive"))
    )
    (net (code "83") (name "Net-(LED84-PadA)") (class "Default")
      (node (ref "LED84") (pin "A") (pinfunction "A_A") (pintype "passive"))
      (node (ref "LED85") (pin "C") (pinfunction "C_C") (pintype "passive"))
    )
    (net (code "84") (name "Net-(LED84-PadC)") (class "Default")
      (node (ref "LED84") (pin "C") (pinfunction "C_C") (pintype "passive"))
      (node (ref "LED85") (pin "A") (pinfunction "A_A") (pintype "passive"))
    )
    (net (code "85") (name "Net-(LED86-PadA)") (class "Default")
      (node (ref "LED86") (pin "A") (pinfunction "A_A") (pintype "passive"))
      (node (ref "LED87") (pin "C") (pinfunction "C_C") (pintype "passive"))
    )
    (net (code "86") (name "Net-(LED86-PadC)") (class "Default")
      (node (ref "LED86") (pin "C") (pinfunction "C_C") (pintype "passive"))
      (node (ref "LED87") (pin "A") (pinfunction "A_A") (pintype "passive"))
    )
    (net (code "87") (name "Net-(LED88-PadA)") (class "Default")
      (node (ref "LED88") (pin "A") (pinfunction "A_A") (pintype "passive"))
      (node (ref "LED89") (pin "C") (pinfunction "C_C") (pintype "passive"))
    )
    (net (code "88") (name "Net-(LED88-PadC)") (class "Default")
      (node (ref "LED88") (pin "C") (pinfunction "C_C") (pintype "passive"))
      (node (ref "LED89") (pin "A") (pinfunction "A_A") (pintype "passive"))
    )
    (net (code "89") (name "Net-(LED90-PadA)") (class "Default")
      (node (ref "LED90") (pin "A") (pinfunction "A_A") (pintype "passive"))
      (node (ref "LED91") (pin "C") (pinfunction "C_C") (pintype "passive"))
    )
    (net (code "90") (name "Net-(LED90-PadC)") (class "Default")
      (node (ref "LED90") (pin "C") (pinfunction "C_C") (pintype "passive"))
      (node (ref "LED91") (pin "A") (pinfunction "A_A") (pintype "passive"))
    )
    (net (code "91") (name "Net-(LED92-PadA)") (class "Default")
      (node (ref "LED92") (pin "A") (pinfunction "A_A") (pintype "passive"))
      (node (ref "LED93") (pin "C") (pinfunction "C_C") (pintype "passive"))
    )
    (net (code "92") (name "Net-(LED92-PadC)") (class "Default")
      (node (ref "LED92") (pin "C") (pinfunction "C_C") (pintype "passive"))
      (node (ref "LED93") (pin "A") (pinfunction "A_A") (pintype "passive"))
    )
    (net (code "93") (name "Net-(LED94-PadA)") (class "Default")
      (node (ref "LED94") (pin "A") (pinfunction "A_A") (pintype "passive"))
      (node (ref "LED95") (pin "C") (pinfunction "C_C") (pintype "passive"))
    )
    (net (code "94") (name "Net-(LED94-PadC)") (class "Default")
      (node (ref "LED94") (pin "C") (pinfunction "C_C") (pintype "passive"))
      (node (ref "LED95") (pin "A") (pinfunction "A_A") (pintype "passive"))
    )
    (net (code "95") (name "Net-(LED96-PadA)") (class "Default")
      (node (ref "LED96") (pin "A") (pinfunction "A_A") (pintype "passive"))
      (node (ref "LED97") (pin "C") (pinfunction "C_C") (pintype "passive"))
    )
    (net (code "96") (name "Net-(LED96-PadC)") (class "Default")
      (node (ref "LED96") (pin "C") (pinfunction "C_C") (pintype "passive"))
      (node (ref "LED97") (pin "A") (pinfunction "A_A") (pintype "passive"))
    )
    (net (code "97") (name "Net-(LED98-PadA)") (class "Default")
      (node (ref "LED98") (pin "A") (pinfunction "A_A") (pintype "passive"))
      (node (ref "LED99") (pin "C") (pinfunction "C_C") (pintype "passive"))
    )
    (net (code "98") (name "Net-(LED98-PadC)") (class "Default")
      (node (ref "LED98") (pin "C") (pinfunction "C_C") (pintype "passive"))
      (node (ref "LED99") (pin "A") (pinfunction "A_A") (pintype "passive"))
    )
    (net (code "99") (name "Net-(LED100-PadA)") (class "Default")
      (node (ref "LED100") (pin "A") (pinfunction "A_A") (pintype "passive"))
      (node (ref "LED101") (pin "C") (pinfunction "C_C") (pintype "passive"))
    )
    (net (code "100") (name "Net-(LED100-PadC)") (class "Default")
      (node (ref "LED100") (pin "C") (pinfunction "C_C") (pintype "passive"))
      (node (ref "LED101") (pin "A") (pinfunction "A_A") (pintype "passive"))
    )
    (net (code "101") (name "Net-(LED102-PadA)") (class "Default")
      (node (ref "LED102") (pin "A") (pinfunction "A_A") (pintype "passive"))
      (node (ref "LED103") (pin "C") (pinfunction "C_C") (pintype "passive"))
    )
    (net (code "102") (name "Net-(LED102-PadC)") (class "Default")
      (node (ref "LED102") (pin "C") (pinfunction "C_C") (pintype "passive"))
      (node (ref "LED103") (pin "A") (pinfunction "A_A") (pintype "passive"))
    )
    (net (code "103") (name "Net-(LED104-PadA)") (class "Default")
      (node (ref "LED104") (pin "A") (pinfunction "A_A") (pintype "passive"))
      (node (ref "LED105") (pin "C") (pinfunction "C_C") (pintype "passive"))
    )
    (net (code "104") (name "Net-(LED104-PadC)") (class "Default")
      (node (ref "LED104") (pin "C") (pinfunction "C_C") (pintype "passive"))
      (node (ref "LED105") (pin "A") (pinfunction "A_A") (pintype "passive"))
    )
    (net (code "105") (name "Net-(LED106-PadA)") (class "Default")
      (node (ref "LED106") (pin "A") (pinfunction "A_A") (pintype "passive"))
      (node (ref "LED107") (pin "C") (pinfunction "C_C") (pintype "passive"))
    )
    (net (code "106") (name "Net-(LED106-PadC)") (class "Default")
      (node (ref "LED106") (pin "C") (pinfunction "C_C") (pintype "passive"))
      (node (ref "LED107") (pin "A") (pinfunction "A_A") (pintype "passive"))
    )
    (net (code "107") (name "Net-(LED108-PadA)") (class "Default")
      (node (ref "LED108") (pin "A") (pinfunction "A_A") (pintype "passive"))
      (node (ref "LED109") (pin "C") (pinfunction "C_C") (pintype "passive"))
    )
    (net (code "108") (name "Net-(LED108-PadC)") (class "Default")
      (node (ref "LED108") (pin "C") (pinfunction "C_C") (pintype "passive"))
      (node (ref "LED109") (pin "A") (pinfunction "A_A") (pintype "passive"))
    )
    (net (code "109") (name "Net-(LED110-PadA)") (class "Default")
      (node (ref "LED110") (pin "A") (pinfunction "A_A") (pintype "passive"))
      (node (ref "LED111") (pin "C") (pinfunction "C_C") (pintype "passive"))
    )
    (net (code "110") (name "Net-(LED110-PadC)") (class "Default")
      (node (ref "LED110") (pin "C") (pinfunction "C_C") (pintype "passive"))
      (node (ref "LED111") (pin "A") (pinfunction "A_A") (pintype "passive"))
    )
    (net (code "111") (name "Net-(LED112-PadA)") (class "Default")
      (node (ref "LED112") (pin "A") (pinfunction "A_A") (pintype "passive"))
      (node (ref "LED113") (pin "C") (pinfunction "C_C") (pintype "passive"))
    )
    (net (code "112") (name "Net-(LED112-PadC)") (class "Default")
      (node (ref "LED112") (pin "C") (pinfunction "C_C") (pintype "passive"))
      (node (ref "LED113") (pin "A") (pinfunction "A_A") (pintype "passive"))
    )
    (net (code "113") (name "Net-(LED114-PadA)") (class "Default")
      (node (ref "LED114") (pin "A") (pinfunction "A_A") (pintype "passive"))
      (node (ref "LED115") (pin "C") (pinfunction "C_C") (pintype "passive"))
    )
    (net (code "114") (name "Net-(LED114-PadC)") (class "Default")
      (node (ref "LED114") (pin "C") (pinfunction "C_C") (pintype "passive"))
      (node (ref "LED115") (pin "A") (pinfunction "A_A") (pintype "passive"))
    )
    (net (code "115") (name "Net-(LED116-PadA)") (class "Default")
      (node (ref "LED116") (pin "A") (pinfunction "A_A") (pintype "passive"))
      (node (ref "LED117") (pin "C") (pinfunction "C_C") (pintype "passive"))
    )
    (net (code "116") (name "Net-(LED116-PadC)") (class "Default")
      (node (ref "LED116") (pin "C") (pinfunction "C_C") (pintype "passive"))
      (node (ref "LED117") (pin "A") (pinfunction "A_A") (pintype "passive"))
    )
    (net (code "117") (name "Net-(LED118-PadA)") (class "Default")
      (node (ref "LED118") (pin "A") (pinfunction "A_A") (pintype "passive"))
      (node (ref "LED119") (pin "C") (pinfunction "C_C") (pintype "passive"))
    )
    (net (code "118") (name "Net-(LED118-PadC)") (class "Default")
      (node (ref "LED118") (pin "C") (pinfunction "C_C") (pintype "passive"))
      (node (ref "LED119") (pin "A") (pinfunction "A_A") (pintype "passive"))
    )
    (net (code "119") (name "Net-(LED120-PadA)") (class "Default")
      (node (ref "LED120") (pin "A") (pinfunction "A_A") (pintype "passive"))
      (node (ref "LED61") (pin "C") (pinfunction "C_C") (pintype "passive"))
    )
    (net (code "120") (name "Net-(LED120-PadC)") (class "Default")
      (node (ref "LED120") (pin "C") (pinfunction "C_C") (pintype "passive"))
      (node (ref "LED61") (pin "A") (pinfunction "A_A") (pintype "passive"))
    )
    (net (code "121") (name "Net-(LED121-PadA)") (class "Default")
      (node (ref "LED121") (pin "A") (pinfunction "A_A") (pintype "passive"))
      (node (ref "LED122") (pin "C") (pinfunction "C_C") (pintype "passive"))
    )
    (net (code "122") (name "Net-(LED121-PadC)") (class "Default")
      (node (ref "LED121") (pin "C") (pinfunction "C_C") (pintype "passive"))
      (node (ref "LED122") (pin "A") (pinfunction "A_A") (pintype "passive"))
    )
    (net (code "123") (name "Net-(LED123-PadA)") (class "Default")
      (node (ref "LED123") (pin "A") (pinfunction "A_A") (pintype "passive"))
      (node (ref "LED124") (pin "C") (pinfunction "C_C") (pintype "passive"))
    )
    (net (code "124") (name "Net-(LED123-PadC)") (class "Default")
      (node (ref "LED123") (pin "C") (pinfunction "C_C") (pintype "passive"))
      (node (ref "LED124") (pin "A") (pinfunction "A_A") (pintype "passive"))
    )
    (net (code "125") (name "Net-(LED125-PadA)") (class "Default")
      (node (ref "LED125") (pin "A") (pinfunction "A_A") (pintype "passive"))
      (node (ref "LED126") (pin "C") (pinfunction "C_C") (pintype "passive"))
    )
    (net (code "126") (name "Net-(LED125-PadC)") (class "Default")
      (node (ref "LED125") (pin "C") (pinfunction "C_C") (pintype "passive"))
      (node (ref "LED126") (pin "A") (pinfunction "A_A") (pintype "passive"))
    )
    (net (code "127") (name "Net-(LED127-PadA)") (class "Default")
      (node (ref "LED127") (pin "A") (pinfunction "A_A") (pintype "passive"))
      (node (ref "LED128") (pin "C") (pinfunction "C_C") (pintype "passive"))
    )
    (net (code "128") (name "Net-(LED127-PadC)") (class "Default")
      (node (ref "LED127") (pin "C") (pinfunction "C_C") (pintype "passive"))
      (node (ref "LED128") (pin "A") (pinfunction "A_A") (pintype "passive"))
    )
    (net (code "129") (name "Net-(LED129-PadA)") (class "Default")
      (node (ref "LED129") (pin "A") (pinfunction "A_A") (pintype "passive"))
      (node (ref "LED130") (pin "C") (pinfunction "C_C") (pintype "passive"))
    )
    (net (code "130") (name "Net-(LED129-PadC)") (class "Default")
      (node (ref "LED129") (pin "C") (pinfunction "C_C") (pintype "passive"))
      (node (ref "LED130") (pin "A") (pinfunction "A_A") (pintype "passive"))
    )
    (net (code "131") (name "Net-(LED131-PadA)") (class "Default")
      (node (ref "LED131") (pin "A") (pinfunction "A_A") (pintype "passive"))
      (node (ref "LED132") (pin "C") (pinfunction "C_C") (pintype "passive"))
    )
    (net (code "132") (name "Net-(LED131-PadC)") (class "Default")
      (node (ref "LED131") (pin "C") (pinfunction "C_C") (pintype "passive"))
      (node (ref "LED132") (pin "A") (pinfunction "A_A") (pintype "passive"))
    )
    (net (code "133") (name "Net-(LED133-PadA)") (class "Default")
      (node (ref "LED133") (pin "A") (pinfunction "A_A") (pintype "passive"))
      (node (ref "LED134") (pin "C") (pinfunction "C_C") (pintype "passive"))
    )
    (net (code "134") (name "Net-(LED133-PadC)") (class "Default")
      (node (ref "LED133") (pin "C") (pinfunction "C_C") (pintype "passive"))
      (node (ref "LED134") (pin "A") (pinfunction "A_A") (pintype "passive"))
    )
    (net (code "135") (name "Net-(LED135-PadA)") (class "Default")
      (node (ref "LED135") (pin "A") (pinfunction "A_A") (pintype "passive"))
      (node (ref "LED136") (pin "C") (pinfunction "C_C") (pintype "passive"))
    )
    (net (code "136") (name "Net-(LED135-PadC)") (class "Default")
      (node (ref "LED135") (pin "C") (pinfunction "C_C") (pintype "passive"))
      (node (ref "LED136") (pin "A") (pinfunction "A_A") (pintype "passive"))
    )
    (net (code "137") (name "Net-(LED137-PadA)") (class "Default")
      (node (ref "LED137") (pin "A") (pinfunction "A_A") (pintype "passive"))
      (node (ref "LED138") (pin "C") (pinfunction "C_C") (pintype "passive"))
    )
    (net (code "138") (name "Net-(LED137-PadC)") (class "Default")
      (node (ref "LED137") (pin "C") (pinfunction "C_C") (pintype "passive"))
      (node (ref "LED138") (pin "A") (pinfunction "A_A") (pintype "passive"))
    )
    (net (code "139") (name "Net-(LED139-PadA)") (class "Default")
      (node (ref "LED139") (pin "A") (pinfunction "A_A") (pintype "passive"))
      (node (ref "LED140") (pin "C") (pinfunction "C_C") (pintype "passive"))
    )
    (net (code "140") (name "Net-(LED139-PadC)") (class "Default")
      (node (ref "LED139") (pin "C") (pinfunction "C_C") (pintype "passive"))
      (node (ref "LED140") (pin "A") (pinfunction "A_A") (pintype "passive"))
    )
    (net (code "141") (name "Net-(LED141-PadA)") (class "Default")
      (node (ref "LED141") (pin "A") (pinfunction "A_A") (pintype "passive"))
      (node (ref "LED142") (pin "C") (pinfunction "C_C") (pintype "passive"))
    )
    (net (code "142") (name "Net-(LED141-PadC)") (class "Default")
      (node (ref "LED141") (pin "C") (pinfunction "C_C") (pintype "passive"))
      (node (ref "LED142") (pin "A") (pinfunction "A_A") (pintype "passive"))
    )
    (net (code "143") (name "Net-(LED143-PadA)") (class "Default")
      (node (ref "LED143") (pin "A") (pinfunction "A_A") (pintype "passive"))
      (node (ref "LED144") (pin "C") (pinfunction "C_C") (pintype "passive"))
    )
    (net (code "144") (name "Net-(LED143-PadC)") (class "Default")
      (node (ref "LED143") (pin "C") (pinfunction "C_C") (pintype "passive"))
      (node (ref "LED144") (pin "A") (pinfunction "A_A") (pintype "passive"))
    )
    (net (code "145") (name "Net-(LED145-PadA)") (class "Default")
      (node (ref "LED145") (pin "A") (pinfunction "A_A") (pintype "passive"))
      (node (ref "LED146") (pin "C") (pinfunction "C_C") (pintype "passive"))
    )
    (net (code "146") (name "Net-(LED145-PadC)") (class "Default")
      (node (ref "LED145") (pin "C") (pinfunction "C_C") (pintype "passive"))
      (node (ref "LED146") (pin "A") (pinfunction "A_A") (pintype "passive"))
    )
    (net (code "147") (name "Net-(LED147-PadA)") (class "Default")
      (node (ref "LED147") (pin "A") (pinfunction "A_A") (pintype "passive"))
      (node (ref "LED148") (pin "C") (pinfunction "C_C") (pintype "passive"))
    )
    (net (code "148") (name "Net-(LED147-PadC)") (class "Default")
      (node (ref "LED147") (pin "C") (pinfunction "C_C") (pintype "passive"))
      (node (ref "LED148") (pin "A") (pinfunction "A_A") (pintype "passive"))
    )
    (net (code "149") (name "Net-(LED149-PadA)") (class "Default")
      (node (ref "LED149") (pin "A") (pinfunction "A_A") (pintype "passive"))
      (node (ref "LED150") (pin "C") (pinfunction "C_C") (pintype "passive"))
    )
    (net (code "150") (name "Net-(LED149-PadC)") (class "Default")
      (node (ref "LED149") (pin "C") (pinfunction "C_C") (pintype "passive"))
      (node (ref "LED150") (pin "A") (pinfunction "A_A") (pintype "passive"))
    )
    (net (code "151") (name "Net-(LED151-PadA)") (class "Default")
      (node (ref "LED151") (pin "A") (pinfunction "A_A") (pintype "passive"))
      (node (ref "LED152") (pin "C") (pinfunction "C_C") (pintype "passive"))
    )
    (net (code "152") (name "Net-(LED151-PadC)") (class "Default")
      (node (ref "LED151") (pin "C") (pinfunction "C_C") (pintype "passive"))
      (node (ref "LED152") (pin "A") (pinfunction "A_A") (pintype "passive"))
    )
    (net (code "153") (name "Net-(LED153-PadA)") (class "Default")
      (node (ref "LED153") (pin "A") (pinfunction "A_A") (pintype "passive"))
      (node (ref "LED154") (pin "C") (pinfunction "C_C") (pintype "passive"))
    )
    (net (code "154") (name "Net-(LED153-PadC)") (class "Default")
      (node (ref "LED153") (pin "C") (pinfunction "C_C") (pintype "passive"))
      (node (ref "LED154") (pin "A") (pinfunction "A_A") (pintype "passive"))
    )
    (net (code "155") (name "Net-(LED155-PadA)") (class "Default")
      (node (ref "LED155") (pin "A") (pinfunction "A_A") (pintype "passive"))
      (node (ref "LED156") (pin "C") (pinfunction "C_C") (pintype "passive"))
    )
    (net (code "156") (name "Net-(LED155-PadC)") (class "Default")
      (node (ref "LED155") (pin "C") (pinfunction "C_C") (pintype "passive"))
      (node (ref "LED156") (pin "A") (pinfunction "A_A") (pintype "passive"))
    )
    (net (code "157") (name "Net-(LED157-PadA)") (class "Default")
      (node (ref "LED157") (pin "A") (pinfunction "A_A") (pintype "passive"))
      (node (ref "LED158") (pin "C") (pinfunction "C_C") (pintype "passive"))
    )
    (net (code "158") (name "Net-(LED157-PadC)") (class "Default")
      (node (ref "LED157") (pin "C") (pinfunction "C_C") (pintype "passive"))
      (node (ref "LED158") (pin "A") (pinfunction "A_A") (pintype "passive"))
    )
    (net (code "159") (name "Net-(LED159-PadA)") (class "Default")
      (node (ref "LED159") (pin "A") (pinfunction "A_A") (pintype "passive"))
      (node (ref "LED160") (pin "C") (pinfunction "C_C") (pintype "passive"))
    )
    (net (code "160") (name "Net-(LED159-PadC)") (class "Default")
      (node (ref "LED159") (pin "C") (pinfunction "C_C") (pintype "passive"))
      (node (ref "LED160") (pin "A") (pinfunction "A_A") (pintype "passive"))
    )
    (net (code "161") (name "Net-(LED161-PadA)") (class "Default")
      (node (ref "LED161") (pin "A") (pinfunction "A_A") (pintype "passive"))
      (node (ref "LED162") (pin "C") (pinfunction "C_C") (pintype "passive"))
    )
    (net (code "162") (name "Net-(LED161-PadC)") (class "Default")
      (node (ref "LED161") (pin "C") (pinfunction "C_C") (pintype "passive"))
      (node (ref "LED162") (pin "A") (pinfunction "A_A") (pintype "passive"))
    )
    (net (code "163") (name "Net-(LED163-PadA)") (class "Default")
      (node (ref "LED163") (pin "A") (pinfunction "A_A") (pintype "passive"))
      (node (ref "LED164") (pin "C") (pinfunction "C_C") (pintype "passive"))
    )
    (net (code "164") (name "Net-(LED163-PadC)") (class "Default")
      (node (ref "LED163") (pin "C") (pinfunction "C_C") (pintype "passive"))
      (node (ref "LED164") (pin "A") (pinfunction "A_A") (pintype "passive"))
    )
    (net (code "165") (name "Net-(LED165-PadA)") (class "Default")
      (node (ref "LED165") (pin "A") (pinfunction "A_A") (pintype "passive"))
      (node (ref "LED166") (pin "C") (pinfunction "C_C") (pintype "passive"))
    )
    (net (code "166") (name "Net-(LED165-PadC)") (class "Default")
      (node (ref "LED165") (pin "C") (pinfunction "C_C") (pintype "passive"))
      (node (ref "LED166") (pin "A") (pinfunction "A_A") (pintype "passive"))
    )
    (net (code "167") (name "Net-(LED167-PadA)") (class "Default")
      (node (ref "LED167") (pin "A") (pinfunction "A_A") (pintype "passive"))
      (node (ref "LED168") (pin "C") (pinfunction "C_C") (pintype "passive"))
    )
    (net (code "168") (name "Net-(LED167-PadC)") (class "Default")
      (node (ref "LED167") (pin "C") (pinfunction "C_C") (pintype "passive"))
      (node (ref "LED168") (pin "A") (pinfunction "A_A") (pintype "passive"))
    )
    (net (code "169") (name "Net-(LED169-PadA)") (class "Default")
      (node (ref "LED169") (pin "A") (pinfunction "A_A") (pintype "passive"))
      (node (ref "LED170") (pin "C") (pinfunction "C_C") (pintype "passive"))
    )
    (net (code "170") (name "Net-(LED169-PadC)") (class "Default")
      (node (ref "LED169") (pin "C") (pinfunction "C_C") (pintype "passive"))
      (node (ref "LED170") (pin "A") (pinfunction "A_A") (pintype "passive"))
    )
    (net (code "171") (name "Net-(LED171-PadA)") (class "Default")
      (node (ref "LED171") (pin "A") (pinfunction "A_A") (pintype "passive"))
      (node (ref "LED172") (pin "C") (pinfunction "C_C") (pintype "passive"))
    )
    (net (code "172") (name "Net-(LED171-PadC)") (class "Default")
      (node (ref "LED171") (pin "C") (pinfunction "C_C") (pintype "passive"))
      (node (ref "LED172") (pin "A") (pinfunction "A_A") (pintype "passive"))
    )
    (net (code "173") (name "Net-(LED173-PadA)") (class "Default")
      (node (ref "LED173") (pin "A") (pinfunction "A_A") (pintype "passive"))
      (node (ref "LED174") (pin "C") (pinfunction "C_C") (pintype "passive"))
    )
    (net (code "174") (name "Net-(LED173-PadC)") (class "Default")
      (node (ref "LED173") (pin "C") (pinfunction "C_C") (pintype "passive"))
      (node (ref "LED174") (pin "A") (pinfunction "A_A") (pintype "passive"))
    )
    (net (code "175") (name "Net-(LED175-PadA)") (class "Default")
      (node (ref "LED175") (pin "A") (pinfunction "A_A") (pintype "passive"))
      (node (ref "LED176") (pin "C") (pinfunction "C_C") (pintype "passive"))
    )
    (net (code "176") (name "Net-(LED175-PadC)") (class "Default")
      (node (ref "LED175") (pin "C") (pinfunction "C_C") (pintype "passive"))
      (node (ref "LED176") (pin "A") (pinfunction "A_A") (pintype "passive"))
    )
    (net (code "177") (name "Net-(LED177-PadA)") (class "Default")
      (node (ref "LED177") (pin "A") (pinfunction "A_A") (pintype "passive"))
      (node (ref "LED178") (pin "C") (pinfunction "C_C") (pintype "passive"))
    )
    (net (code "178") (name "Net-(LED177-PadC)") (class "Default")
      (node (ref "LED177") (pin "C") (pinfunction "C_C") (pintype "passive"))
      (node (ref "LED178") (pin "A") (pinfunction "A_A") (pintype "passive"))
    )
    (net (code "179") (name "Net-(LED179-PadA)") (class "Default")
      (node (ref "LED179") (pin "A") (pinfunction "A_A") (pintype "passive"))
      (node (ref "LED180") (pin "C") (pinfunction "C_C") (pintype "passive"))
    )
    (net (code "180") (name "Net-(LED179-PadC)") (class "Default")
      (node (ref "LED179") (pin "C") (pinfunction "C_C") (pintype "passive"))
      (node (ref "LED180") (pin "A") (pinfunction "A_A") (pintype "passive"))
    )
  )
)
